# S7CAS-PLEIADES-CARTE-MERE_P20_DDR3-Decou.net
KiCad netlist of a schematic drawn in Altium Designer
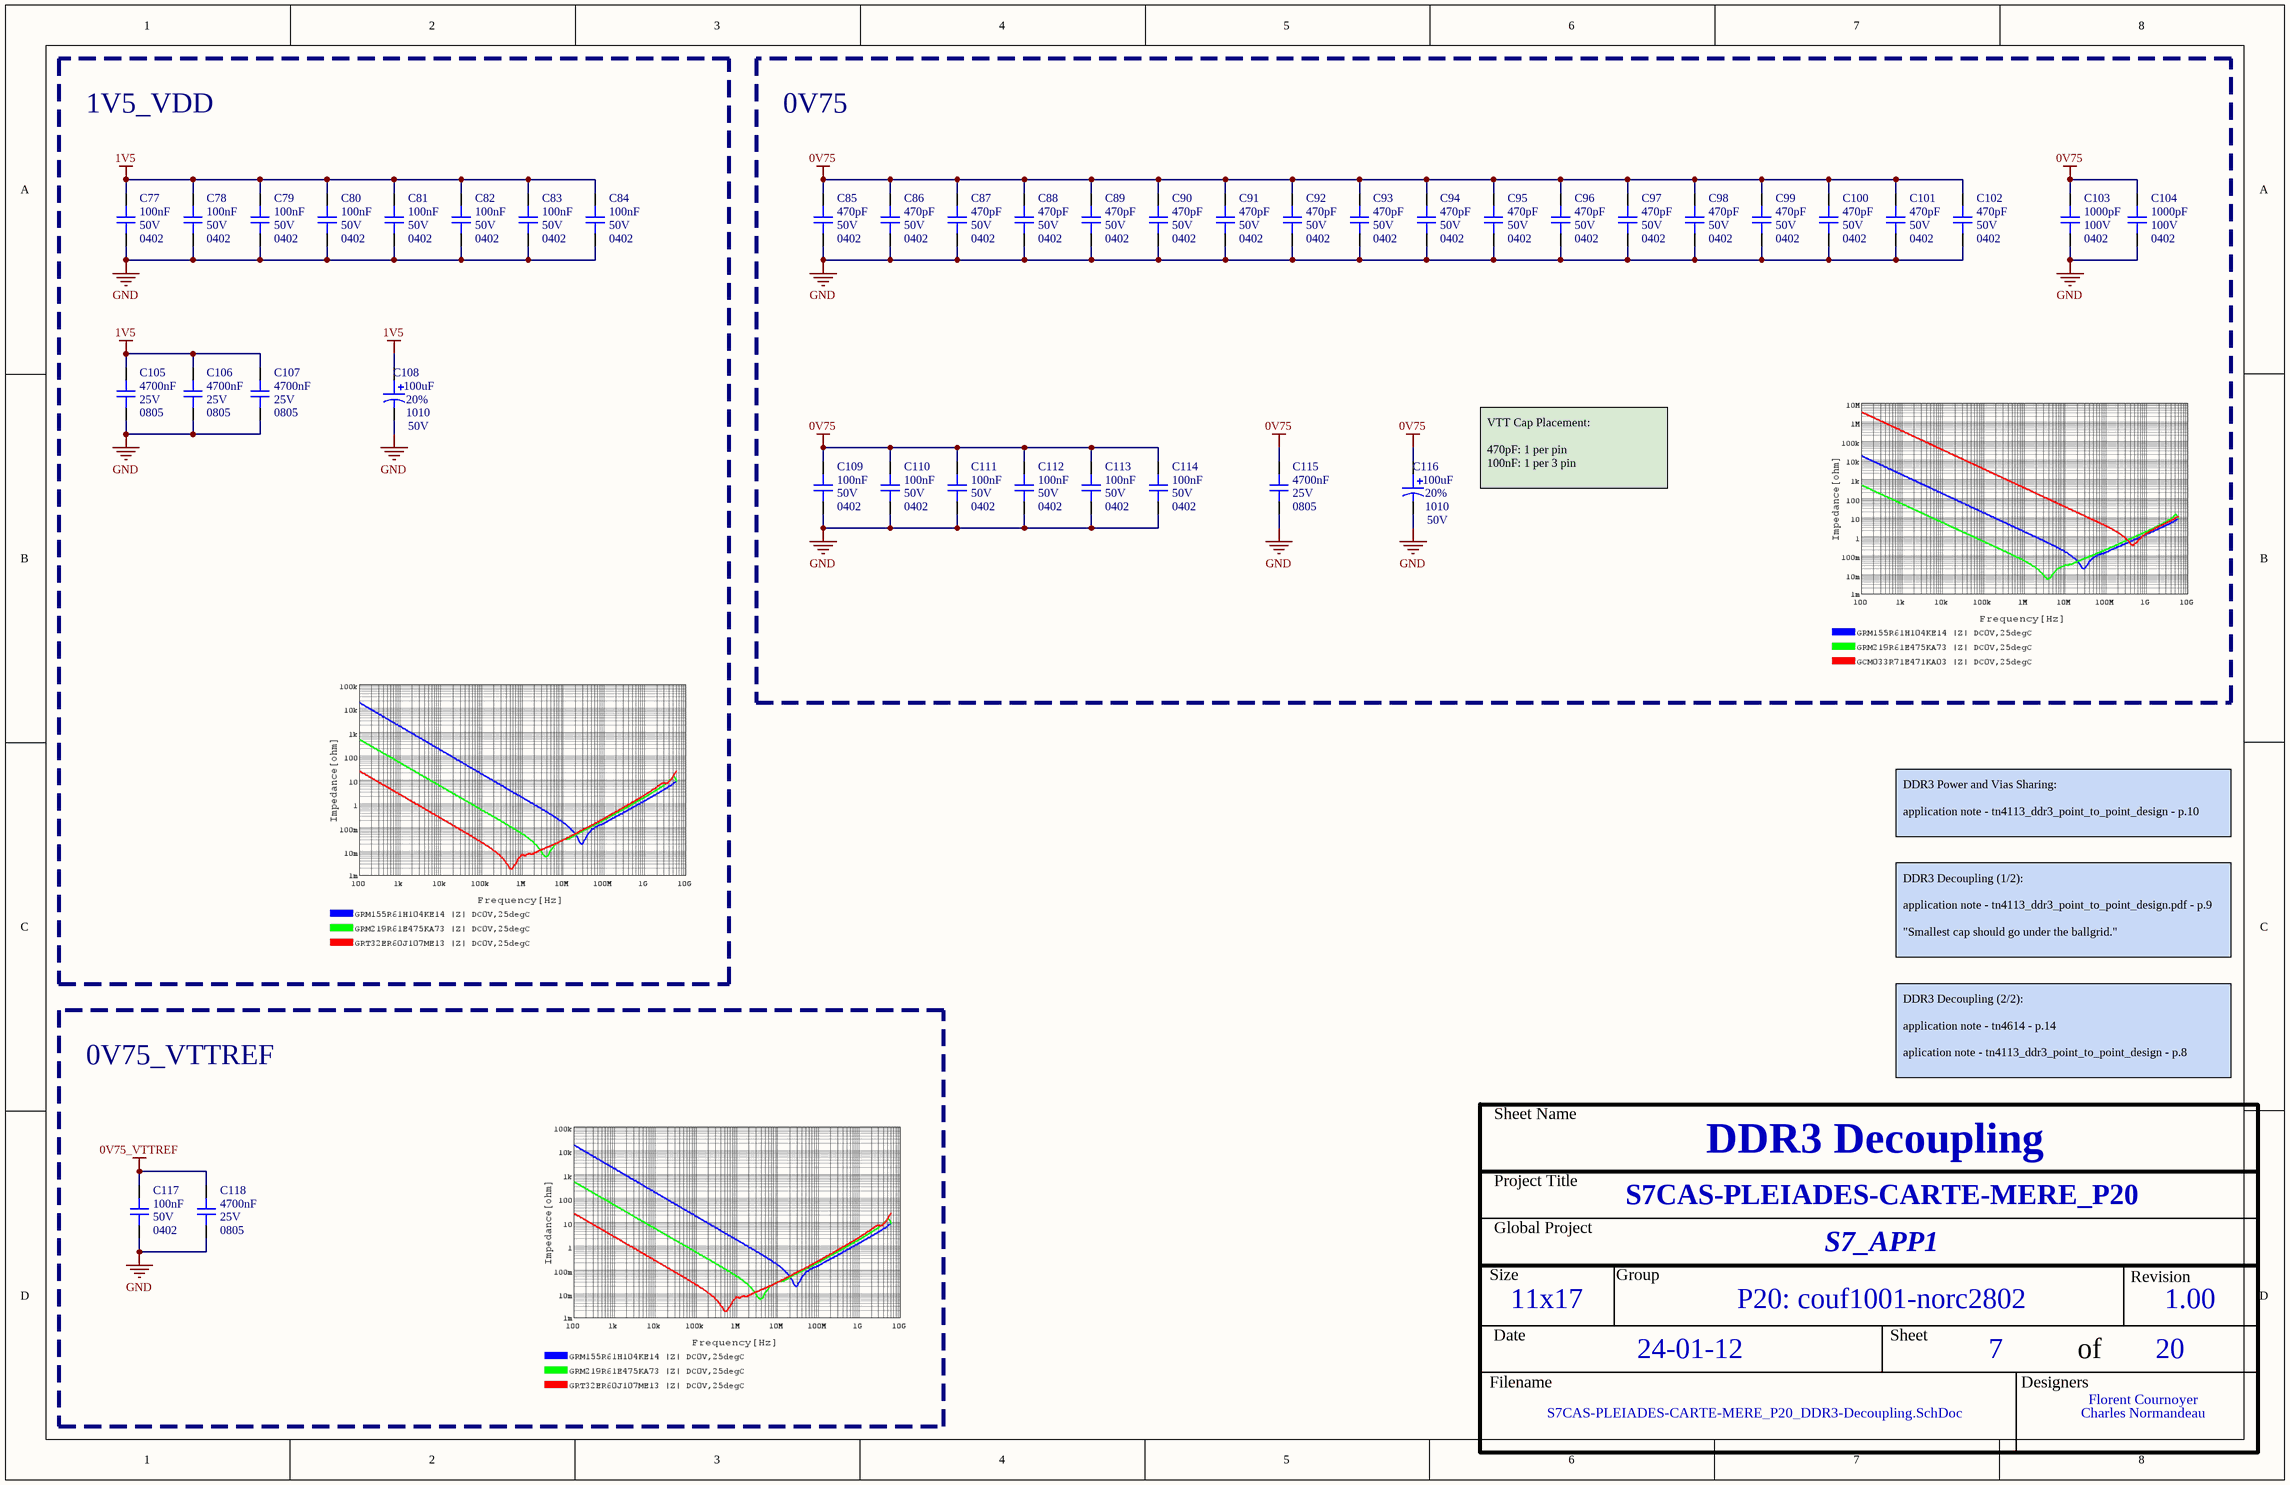
[diagram p0: S7CAS-PLEIADES-CARTE-MERE_P20_DDR3-Decoupling.SchDoc]

(export (version "E")
  (design (tool "Eeschema 10.0.6"))
  (components
    (comp (ref "C77")
      (value "100nF")
      (footprint "CAP_0402")
      (description "CAP - 0402")
      (fields
        (field (name "MFG PART NUMBER") "GRM155R61H104KE14")
        (field (name "VOLTAGE") "50V")
        (field (name "PACKAGE") "0402")
        (field (name "CREATEDBY") "Jonathan Bouchard")
      )
      (libsource (lib "S7CAS_LIB2023") (part "CAP - 0402"))
    )
    (comp (ref "C78")
      (value "100nF")
      (footprint "CAP_0402")
      (description "CAP - 0402")
      (fields
        (field (name "MFG PART NUMBER") "GRM155R61H104KE14")
        (field (name "VOLTAGE") "50V")
        (field (name "PACKAGE") "0402")
        (field (name "CREATEDBY") "Jonathan Bouchard")
      )
      (libsource (lib "S7CAS_LIB2023") (part "CAP - 0402"))
    )
    (comp (ref "C79")
      (value "100nF")
      (footprint "CAP_0402")
      (description "CAP - 0402")
      (fields
        (field (name "MFG PART NUMBER") "GRM155R61H104KE14")
        (field (name "VOLTAGE") "50V")
        (field (name "PACKAGE") "0402")
        (field (name "CREATEDBY") "Jonathan Bouchard")
      )
      (libsource (lib "S7CAS_LIB2023") (part "CAP - 0402"))
    )
    (comp (ref "C80")
      (value "100nF")
      (footprint "CAP_0402")
      (description "CAP - 0402")
      (fields
        (field (name "MFG PART NUMBER") "GRM155R61H104KE14")
        (field (name "VOLTAGE") "50V")
        (field (name "PACKAGE") "0402")
        (field (name "CREATEDBY") "Jonathan Bouchard")
      )
      (libsource (lib "S7CAS_LIB2023") (part "CAP - 0402"))
    )
    (comp (ref "C81")
      (value "100nF")
      (footprint "CAP_0402")
      (description "CAP - 0402")
      (fields
        (field (name "MFG PART NUMBER") "GRM155R61H104KE14")
        (field (name "VOLTAGE") "50V")
        (field (name "PACKAGE") "0402")
        (field (name "CREATEDBY") "Jonathan Bouchard")
      )
      (libsource (lib "S7CAS_LIB2023") (part "CAP - 0402"))
    )
    (comp (ref "C82")
      (value "100nF")
      (footprint "CAP_0402")
      (description "CAP - 0402")
      (fields
        (field (name "MFG PART NUMBER") "GRM155R61H104KE14")
        (field (name "VOLTAGE") "50V")
        (field (name "PACKAGE") "0402")
        (field (name "CREATEDBY") "Jonathan Bouchard")
      )
      (libsource (lib "S7CAS_LIB2023") (part "CAP - 0402"))
    )
    (comp (ref "C83")
      (value "100nF")
      (footprint "CAP_0402")
      (description "CAP - 0402")
      (fields
        (field (name "MFG PART NUMBER") "GRM155R61H104KE14")
        (field (name "VOLTAGE") "50V")
        (field (name "PACKAGE") "0402")
        (field (name "CREATEDBY") "Jonathan Bouchard")
      )
      (libsource (lib "S7CAS_LIB2023") (part "CAP - 0402"))
    )
    (comp (ref "C84")
      (value "100nF")
      (footprint "CAP_0402")
      (description "CAP - 0402")
      (fields
        (field (name "MFG PART NUMBER") "GRM155R61H104KE14")
        (field (name "VOLTAGE") "50V")
        (field (name "PACKAGE") "0402")
        (field (name "CREATEDBY") "Jonathan Bouchard")
      )
      (libsource (lib "S7CAS_LIB2023") (part "CAP - 0402"))
    )
    (comp (ref "C85")
      (value "470pF")
      (footprint "CAP_0402")
      (description "CAP - 0402")
      (fields
        (field (name "MFG PART NUMBER") "GRM1555C1H471GA01")
        (field (name "VOLTAGE") "50V")
        (field (name "PACKAGE") "0402")
        (field (name "CREATEDBY") "Jonathan Bouchard")
      )
      (libsource (lib "S7CAS_LIB2023") (part "CAP - 0402"))
    )
    (comp (ref "C86")
      (value "470pF")
      (footprint "CAP_0402")
      (description "CAP - 0402")
      (fields
        (field (name "MFG PART NUMBER") "GRM1555C1H471GA01")
        (field (name "VOLTAGE") "50V")
        (field (name "PACKAGE") "0402")
        (field (name "CREATEDBY") "Jonathan Bouchard")
      )
      (libsource (lib "S7CAS_LIB2023") (part "CAP - 0402"))
    )
    (comp (ref "C87")
      (value "470pF")
      (footprint "CAP_0402")
      (description "CAP - 0402")
      (fields
        (field (name "MFG PART NUMBER") "GRM1555C1H471GA01")
        (field (name "VOLTAGE") "50V")
        (field (name "PACKAGE") "0402")
        (field (name "CREATEDBY") "Jonathan Bouchard")
      )
      (libsource (lib "S7CAS_LIB2023") (part "CAP - 0402"))
    )
    (comp (ref "C88")
      (value "470pF")
      (footprint "CAP_0402")
      (description "CAP - 0402")
      (fields
        (field (name "MFG PART NUMBER") "GRM1555C1H471GA01")
        (field (name "VOLTAGE") "50V")
        (field (name "PACKAGE") "0402")
        (field (name "CREATEDBY") "Jonathan Bouchard")
      )
      (libsource (lib "S7CAS_LIB2023") (part "CAP - 0402"))
    )
    (comp (ref "C89")
      (value "470pF")
      (footprint "CAP_0402")
      (description "CAP - 0402")
      (fields
        (field (name "MFG PART NUMBER") "GRM1555C1H471GA01")
        (field (name "VOLTAGE") "50V")
        (field (name "PACKAGE") "0402")
        (field (name "CREATEDBY") "Jonathan Bouchard")
      )
      (libsource (lib "S7CAS_LIB2023") (part "CAP - 0402"))
    )
    (comp (ref "C90")
      (value "470pF")
      (footprint "CAP_0402")
      (description "CAP - 0402")
      (fields
        (field (name "MFG PART NUMBER") "GRM1555C1H471GA01")
        (field (name "VOLTAGE") "50V")
        (field (name "PACKAGE") "0402")
        (field (name "CREATEDBY") "Jonathan Bouchard")
      )
      (libsource (lib "S7CAS_LIB2023") (part "CAP - 0402"))
    )
    (comp (ref "C91")
      (value "470pF")
      (footprint "CAP_0402")
      (description "CAP - 0402")
      (fields
        (field (name "MFG PART NUMBER") "GRM1555C1H471GA01")
        (field (name "VOLTAGE") "50V")
        (field (name "PACKAGE") "0402")
        (field (name "CREATEDBY") "Jonathan Bouchard")
      )
      (libsource (lib "S7CAS_LIB2023") (part "CAP - 0402"))
    )
    (comp (ref "C92")
      (value "470pF")
      (footprint "CAP_0402")
      (description "CAP - 0402")
      (fields
        (field (name "MFG PART NUMBER") "GRM1555C1H471GA01")
        (field (name "VOLTAGE") "50V")
        (field (name "PACKAGE") "0402")
        (field (name "CREATEDBY") "Jonathan Bouchard")
      )
      (libsource (lib "S7CAS_LIB2023") (part "CAP - 0402"))
    )
    (comp (ref "C93")
      (value "470pF")
      (footprint "CAP_0402")
      (description "CAP - 0402")
      (fields
        (field (name "MFG PART NUMBER") "GRM1555C1H471GA01")
        (field (name "VOLTAGE") "50V")
        (field (name "PACKAGE") "0402")
        (field (name "CREATEDBY") "Jonathan Bouchard")
      )
      (libsource (lib "S7CAS_LIB2023") (part "CAP - 0402"))
    )
    (comp (ref "C94")
      (value "470pF")
      (footprint "CAP_0402")
      (description "CAP - 0402")
      (fields
        (field (name "MFG PART NUMBER") "GRM1555C1H471GA01")
        (field (name "VOLTAGE") "50V")
        (field (name "PACKAGE") "0402")
        (field (name "CREATEDBY") "Jonathan Bouchard")
      )
      (libsource (lib "S7CAS_LIB2023") (part "CAP - 0402"))
    )
    (comp (ref "C95")
      (value "470pF")
      (footprint "CAP_0402")
      (description "CAP - 0402")
      (fields
        (field (name "MFG PART NUMBER") "GRM1555C1H471GA01")
        (field (name "VOLTAGE") "50V")
        (field (name "PACKAGE") "0402")
        (field (name "CREATEDBY") "Jonathan Bouchard")
      )
      (libsource (lib "S7CAS_LIB2023") (part "CAP - 0402"))
    )
    (comp (ref "C96")
      (value "470pF")
      (footprint "CAP_0402")
      (description "CAP - 0402")
      (fields
        (field (name "MFG PART NUMBER") "GRM1555C1H471GA01")
        (field (name "VOLTAGE") "50V")
        (field (name "PACKAGE") "0402")
        (field (name "CREATEDBY") "Jonathan Bouchard")
      )
      (libsource (lib "S7CAS_LIB2023") (part "CAP - 0402"))
    )
    (comp (ref "C97")
      (value "470pF")
      (footprint "CAP_0402")
      (description "CAP - 0402")
      (fields
        (field (name "MFG PART NUMBER") "GRM1555C1H471GA01")
        (field (name "VOLTAGE") "50V")
        (field (name "PACKAGE") "0402")
        (field (name "CREATEDBY") "Jonathan Bouchard")
      )
      (libsource (lib "S7CAS_LIB2023") (part "CAP - 0402"))
    )
    (comp (ref "C98")
      (value "470pF")
      (footprint "CAP_0402")
      (description "CAP - 0402")
      (fields
        (field (name "MFG PART NUMBER") "GRM1555C1H471GA01")
        (field (name "VOLTAGE") "50V")
        (field (name "PACKAGE") "0402")
        (field (name "CREATEDBY") "Jonathan Bouchard")
      )
      (libsource (lib "S7CAS_LIB2023") (part "CAP - 0402"))
    )
    (comp (ref "C99")
      (value "470pF")
      (footprint "CAP_0402")
      (description "CAP - 0402")
      (fields
        (field (name "MFG PART NUMBER") "GRM1555C1H471GA01")
        (field (name "VOLTAGE") "50V")
        (field (name "PACKAGE") "0402")
        (field (name "CREATEDBY") "Jonathan Bouchard")
      )
      (libsource (lib "S7CAS_LIB2023") (part "CAP - 0402"))
    )
    (comp (ref "C100")
      (value "470pF")
      (footprint "CAP_0402")
      (description "CAP - 0402")
      (fields
        (field (name "MFG PART NUMBER") "GRM1555C1H471GA01")
        (field (name "VOLTAGE") "50V")
        (field (name "PACKAGE") "0402")
        (field (name "CREATEDBY") "Jonathan Bouchard")
      )
      (libsource (lib "S7CAS_LIB2023") (part "CAP - 0402"))
    )
    (comp (ref "C101")
      (value "470pF")
      (footprint "CAP_0402")
      (description "CAP - 0402")
      (fields
        (field (name "MFG PART NUMBER") "GRM1555C1H471GA01")
        (field (name "VOLTAGE") "50V")
        (field (name "PACKAGE") "0402")
        (field (name "CREATEDBY") "Jonathan Bouchard")
      )
      (libsource (lib "S7CAS_LIB2023") (part "CAP - 0402"))
    )
    (comp (ref "C102")
      (value "470pF")
      (footprint "CAP_0402")
      (description "CAP - 0402")
      (fields
        (field (name "MFG PART NUMBER") "GRM1555C1H471GA01")
        (field (name "VOLTAGE") "50V")
        (field (name "PACKAGE") "0402")
        (field (name "CREATEDBY") "Jonathan Bouchard")
      )
      (libsource (lib "S7CAS_LIB2023") (part "CAP - 0402"))
    )
    (comp (ref "C103")
      (value "1000pF")
      (footprint "CAP_0402")
      (description "CAP - 0402")
      (fields
        (field (name "MFG PART NUMBER") "GRM155R72A102KA01")
        (field (name "VOLTAGE") "100V")
        (field (name "PACKAGE") "0402")
        (field (name "CREATEDBY") "Jonathan Bouchard")
      )
      (libsource (lib "S7CAS_LIB2023") (part "CAP - 0402"))
    )
    (comp (ref "C104")
      (value "1000pF")
      (footprint "CAP_0402")
      (description "CAP - 0402")
      (fields
        (field (name "MFG PART NUMBER") "GRM155R72A102KA01")
        (field (name "VOLTAGE") "100V")
        (field (name "PACKAGE") "0402")
        (field (name "CREATEDBY") "Jonathan Bouchard")
      )
      (libsource (lib "S7CAS_LIB2023") (part "CAP - 0402"))
    )
    (comp (ref "C105")
      (value "4700nF")
      (footprint "CAP_0805")
      (description "CAP - 0805")
      (fields
        (field (name "MFG PART NUMBER") "GRM219R61E475KA73")
        (field (name "VOLTAGE") "25V")
        (field (name "PACKAGE") "0805")
        (field (name "CREATEDBY") "Jonathan Bouchard")
      )
      (libsource (lib "S7CAS_LIB2023") (part "CAP - 0805"))
    )
    (comp (ref "C106")
      (value "4700nF")
      (footprint "CAP_0805")
      (description "CAP - 0805")
      (fields
        (field (name "MFG PART NUMBER") "GRM219R61E475KA73")
        (field (name "VOLTAGE") "25V")
        (field (name "PACKAGE") "0805")
        (field (name "CREATEDBY") "Jonathan Bouchard")
      )
      (libsource (lib "S7CAS_LIB2023") (part "CAP - 0805"))
    )
    (comp (ref "C107")
      (value "4700nF")
      (footprint "CAP_0805")
      (description "CAP - 0805")
      (fields
        (field (name "MFG PART NUMBER") "GRM219R61E475KA73")
        (field (name "VOLTAGE") "25V")
        (field (name "PACKAGE") "0805")
        (field (name "CREATEDBY") "Jonathan Bouchard")
      )
      (libsource (lib "S7CAS_LIB2023") (part "CAP - 0805"))
    )
    (comp (ref "C108")
      (value "100uF")
      (footprint "CAP_ALU_1010_vishay")
      (description "CAP - ALU 100uF 20% 50V - 1010")
      (fields
        (field (name "MFG") "Vishay Dale")
        (field (name "MFG PART NUMBER") "MAL215099101E3")
        (field (name "VOLTAGE") "50V")
        (field (name "PACKAGE") "1010")
        (field (name "PRECISION") "20%")
        (field (name "CREATEDBY") "Jonathan Bouchard")
      )
      (libsource (lib "S7CAS_LIB2023") (part "CAP_ALU_MAL215099101E3"))
    )
    (comp (ref "C109")
      (value "100nF")
      (footprint "CAP_0402")
      (description "CAP - 0402")
      (fields
        (field (name "MFG PART NUMBER") "GRM155R61H104KE14")
        (field (name "VOLTAGE") "50V")
        (field (name "PACKAGE") "0402")
        (field (name "CREATEDBY") "Jonathan Bouchard")
      )
      (libsource (lib "S7CAS_LIB2023") (part "CAP - 0402"))
    )
    (comp (ref "C110")
      (value "100nF")
      (footprint "CAP_0402")
      (description "CAP - 0402")
      (fields
        (field (name "MFG PART NUMBER") "GRM155R61H104KE14")
        (field (name "VOLTAGE") "50V")
        (field (name "PACKAGE") "0402")
        (field (name "CREATEDBY") "Jonathan Bouchard")
      )
      (libsource (lib "S7CAS_LIB2023") (part "CAP - 0402"))
    )
    (comp (ref "C111")
      (value "100nF")
      (footprint "CAP_0402")
      (description "CAP - 0402")
      (fields
        (field (name "MFG PART NUMBER") "GRM155R61H104KE14")
        (field (name "VOLTAGE") "50V")
        (field (name "PACKAGE") "0402")
        (field (name "CREATEDBY") "Jonathan Bouchard")
      )
      (libsource (lib "S7CAS_LIB2023") (part "CAP - 0402"))
    )
    (comp (ref "C112")
      (value "100nF")
      (footprint "CAP_0402")
      (description "CAP - 0402")
      (fields
        (field (name "MFG PART NUMBER") "GRM155R61H104KE14")
        (field (name "VOLTAGE") "50V")
        (field (name "PACKAGE") "0402")
        (field (name "CREATEDBY") "Jonathan Bouchard")
      )
      (libsource (lib "S7CAS_LIB2023") (part "CAP - 0402"))
    )
    (comp (ref "C113")
      (value "100nF")
      (footprint "CAP_0402")
      (description "CAP - 0402")
      (fields
        (field (name "MFG PART NUMBER") "GRM155R61H104KE14")
        (field (name "VOLTAGE") "50V")
        (field (name "PACKAGE") "0402")
        (field (name "CREATEDBY") "Jonathan Bouchard")
      )
      (libsource (lib "S7CAS_LIB2023") (part "CAP - 0402"))
    )
    (comp (ref "C114")
      (value "100nF")
      (footprint "CAP_0402")
      (description "CAP - 0402")
      (fields
        (field (name "MFG PART NUMBER") "GRM155R61H104KE14")
        (field (name "VOLTAGE") "50V")
        (field (name "PACKAGE") "0402")
        (field (name "CREATEDBY") "Jonathan Bouchard")
      )
      (libsource (lib "S7CAS_LIB2023") (part "CAP - 0402"))
    )
    (comp (ref "C115")
      (value "4700nF")
      (footprint "CAP_0805")
      (description "CAP - 0805")
      (fields
        (field (name "MFG PART NUMBER") "GRM219R61E475KA73")
        (field (name "VOLTAGE") "25V")
        (field (name "PACKAGE") "0805")
        (field (name "CREATEDBY") "Jonathan Bouchard")
      )
      (libsource (lib "S7CAS_LIB2023") (part "CAP - 0805"))
    )
    (comp (ref "C116")
      (value "100uF")
      (footprint "CAP_ALU_1010_vishay")
      (description "CAP - ALU 100uF 20% 50V - 1010")
      (fields
        (field (name "MFG") "Vishay Dale")
        (field (name "MFG PART NUMBER") "MAL215099101E3")
        (field (name "VOLTAGE") "50V")
        (field (name "PACKAGE") "1010")
        (field (name "PRECISION") "20%")
        (field (name "CREATEDBY") "Jonathan Bouchard")
      )
      (libsource (lib "S7CAS_LIB2023") (part "CAP_ALU_MAL215099101E3"))
    )
    (comp (ref "C117")
      (value "100nF")
      (footprint "CAP_0402")
      (description "CAP - 0402")
      (fields
        (field (name "MFG PART NUMBER") "GRM155R61H104KE14")
        (field (name "VOLTAGE") "50V")
        (field (name "PACKAGE") "0402")
        (field (name "CREATEDBY") "Jonathan Bouchard")
      )
      (libsource (lib "S7CAS_LIB2023") (part "CAP - 0402"))
    )
    (comp (ref "C118")
      (value "4700nF")
      (footprint "CAP_0805")
      (description "CAP - 0805")
      (fields
        (field (name "MFG PART NUMBER") "GRM219R61E475KA73")
        (field (name "VOLTAGE") "25V")
        (field (name "PACKAGE") "0805")
        (field (name "CREATEDBY") "Jonathan Bouchard")
      )
      (libsource (lib "S7CAS_LIB2023") (part "CAP - 0805"))
    )
  )
  (nets
    (net (code "1") (name "0V75") (class "Default")
      (node (ref "C100") (pin "2") (pinfunction "2_2") (pintype "passive"))
      (node (ref "C101") (pin "2") (pinfunction "2_2") (pintype "passive"))
      (node (ref "C102") (pin "2") (pinfunction "2_2") (pintype "passive"))
      (node (ref "C103") (pin "2") (pinfunction "2_2") (pintype "passive"))
      (node (ref "C104") (pin "2") (pinfunction "2_2") (pintype "passive"))
      (node (ref "C109") (pin "2") (pinfunction "2_2") (pintype "passive"))
      (node (ref "C110") (pin "2") (pinfunction "2_2") (pintype "passive"))
      (node (ref "C111") (pin "2") (pinfunction "2_2") (pintype "passive"))
      (node (ref "C112") (pin "2") (pinfunction "2_2") (pintype "passive"))
      (node (ref "C113") (pin "2") (pinfunction "2_2") (pintype "passive"))
      (node (ref "C114") (pin "2") (pinfunction "2_2") (pintype "passive"))
      (node (ref "C115") (pin "2") (pinfunction "2_2") (pintype "passive"))
      (node (ref "C116") (pin "1") (pinfunction "1_1") (pintype "passive"))
      (node (ref "C85") (pin "2") (pinfunction "2_2") (pintype "passive"))
      (node (ref "C86") (pin "2") (pinfunction "2_2") (pintype "passive"))
      (node (ref "C87") (pin "2") (pinfunction "2_2") (pintype "passive"))
      (node (ref "C88") (pin "2") (pinfunction "2_2") (pintype "passive"))
      (node (ref "C89") (pin "2") (pinfunction "2_2") (pintype "passive"))
      (node (ref "C90") (pin "2") (pinfunction "2_2") (pintype "passive"))
      (node (ref "C91") (pin "2") (pinfunction "2_2") (pintype "passive"))
      (node (ref "C92") (pin "2") (pinfunction "2_2") (pintype "passive"))
      (node (ref "C93") (pin "2") (pinfunction "2_2") (pintype "passive"))
      (node (ref "C94") (pin "2") (pinfunction "2_2") (pintype "passive"))
      (node (ref "C95") (pin "2") (pinfunction "2_2") (pintype "passive"))
      (node (ref "C96") (pin "2") (pinfunction "2_2") (pintype "passive"))
      (node (ref "C97") (pin "2") (pinfunction "2_2") (pintype "passive"))
      (node (ref "C98") (pin "2") (pinfunction "2_2") (pintype "passive"))
      (node (ref "C99") (pin "2") (pinfunction "2_2") (pintype "passive"))
    )
    (net (code "2") (name "0V75_VTTREF") (class "Default")
      (node (ref "C117") (pin "2") (pinfunction "2_2") (pintype "passive"))
      (node (ref "C118") (pin "2") (pinfunction "2_2") (pintype "passive"))
    )
    (net (code "3") (name "1V5") (class "Default")
      (node (ref "C105") (pin "2") (pinfunction "2_2") (pintype "passive"))
      (node (ref "C106") (pin "2") (pinfunction "2_2") (pintype "passive"))
      (node (ref "C107") (pin "2") (pinfunction "2_2") (pintype "passive"))
      (node (ref "C108") (pin "1") (pinfunction "1_1") (pintype "passive"))
      (node (ref "C77") (pin "2") (pinfunction "2_2") (pintype "passive"))
      (node (ref "C78") (pin "2") (pinfunction "2_2") (pintype "passive"))
      (node (ref "C79") (pin "2") (pinfunction "2_2") (pintype "passive"))
      (node (ref "C80") (pin "2") (pinfunction "2_2") (pintype "passive"))
      (node (ref "C81") (pin "2") (pinfunction "2_2") (pintype "passive"))
      (node (ref "C82") (pin "2") (pinfunction "2_2") (pintype "passive"))
      (node (ref "C83") (pin "2") (pinfunction "2_2") (pintype "passive"))
      (node (ref "C84") (pin "2") (pinfunction "2_2") (pintype "passive"))
    )
    (net (code "4") (name "GND") (class "Default")
      (node (ref "C100") (pin "1") (pinfunction "1_1") (pintype "passive"))
      (node (ref "C101") (pin "1") (pinfunction "1_1") (pintype "passive"))
      (node (ref "C102") (pin "1") (pinfunction "1_1") (pintype "passive"))
      (node (ref "C103") (pin "1") (pinfunction "1_1") (pintype "passive"))
      (node (ref "C104") (pin "1") (pinfunction "1_1") (pintype "passive"))
      (node (ref "C105") (pin "1") (pinfunction "1_1") (pintype "passive"))
      (node (ref "C106") (pin "1") (pinfunction "1_1") (pintype "passive"))
      (node (ref "C107") (pin "1") (pinfunction "1_1") (pintype "passive"))
      (node (ref "C108") (pin "2") (pinfunction "2_2") (pintype "passive"))
      (node (ref "C109") (pin "1") (pinfunction "1_1") (pintype "passive"))
      (node (ref "C110") (pin "1") (pinfunction "1_1") (pintype "passive"))
      (node (ref "C111") (pin "1") (pinfunction "1_1") (pintype "passive"))
      (node (ref "C112") (pin "1") (pinfunction "1_1") (pintype "passive"))
      (node (ref "C113") (pin "1") (pinfunction "1_1") (pintype "passive"))
      (node (ref "C114") (pin "1") (pinfunction "1_1") (pintype "passive"))
      (node (ref "C115") (pin "1") (pinfunction "1_1") (pintype "passive"))
      (node (ref "C116") (pin "2") (pinfunction "2_2") (pintype "passive"))
      (node (ref "C117") (pin "1") (pinfunction "1_1") (pintype "passive"))
      (node (ref "C118") (pin "1") (pinfunction "1_1") (pintype "passive"))
      (node (ref "C77") (pin "1") (pinfunction "1_1") (pintype "passive"))
      (node (ref "C78") (pin "1") (pinfunction "1_1") (pintype "passive"))
      (node (ref "C79") (pin "1") (pinfunction "1_1") (pintype "passive"))
      (node (ref "C80") (pin "1") (pinfunction "1_1") (pintype "passive"))
      (node (ref "C81") (pin "1") (pinfunction "1_1") (pintype "passive"))
      (node (ref "C82") (pin "1") (pinfunction "1_1") (pintype "passive"))
      (node (ref "C83") (pin "1") (pinfunction "1_1") (pintype "passive"))
      (node (ref "C84") (pin "1") (pinfunction "1_1") (pintype "passive"))
      (node (ref "C85") (pin "1") (pinfunction "1_1") (pintype "passive"))
      (node (ref "C86") (pin "1") (pinfunction "1_1") (pintype "passive"))
      (node (ref "C87") (pin "1") (pinfunction "1_1") (pintype "passive"))
      (node (ref "C88") (pin "1") (pinfunction "1_1") (pintype "passive"))
      (node (ref "C89") (pin "1") (pinfunction "1_1") (pintype "passive"))
      (node (ref "C90") (pin "1") (pinfunction "1_1") (pintype "passive"))
      (node (ref "C91") (pin "1") (pinfunction "1_1") (pintype "passive"))
      (node (ref "C92") (pin "1") (pinfunction "1_1") (pintype "passive"))
      (node (ref "C93") (pin "1") (pinfunction "1_1") (pintype "passive"))
      (node (ref "C94") (pin "1") (pinfunction "1_1") (pintype "passive"))
      (node (ref "C95") (pin "1") (pinfunction "1_1") (pintype "passive"))
      (node (ref "C96") (pin "1") (pinfunction "1_1") (pintype "passive"))
      (node (ref "C97") (pin "1") (pinfunction "1_1") (pintype "passive"))
      (node (ref "C98") (pin "1") (pinfunction "1_1") (pintype "passive"))
      (node (ref "C99") (pin "1") (pinfunction "1_1") (pintype "passive"))
    )
  )
)
